# A-15430.net
KiCad netlist of a schematic drawn in EAGLE
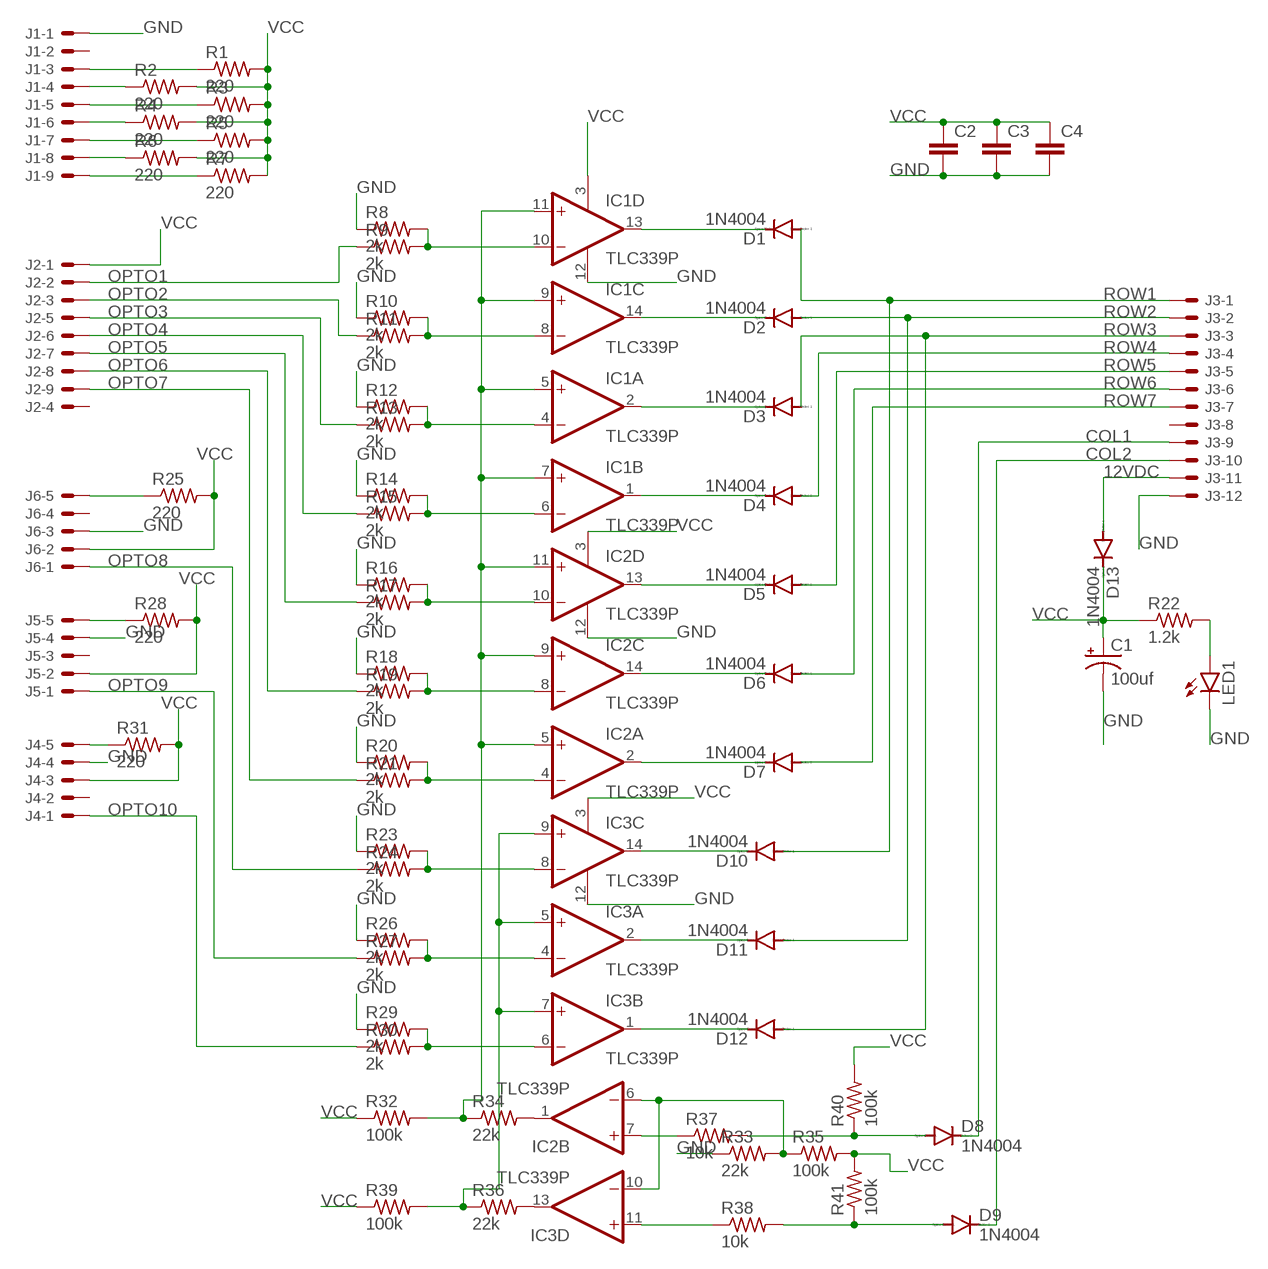
[diagram p0: schematic, sheet 1]

(export (version "E")
  (design (tool "Eeschema 10.0.6"))
  (components
    (comp (ref "C1")
      (value "100uf")
      (footprint "eagle-import:E2,5-5")
      (libsource (lib "eagle-import") (part "CPOL-USE2.5-5"))
    )
    (comp (ref "C2")
      (value "C2.5/4")
      (footprint "eagle-import:C2.5-4")
      (libsource (lib "eagle-import") (part "C2.5/4"))
    )
    (comp (ref "C3")
      (value "C2.5/4")
      (footprint "eagle-import:C2.5-4")
      (libsource (lib "eagle-import") (part "C2.5/4"))
    )
    (comp (ref "C4")
      (value "C2.5/4")
      (footprint "eagle-import:C2.5-4")
      (libsource (lib "eagle-import") (part "C2.5/4"))
    )
    (comp (ref "D1")
      (value "1N4004")
      (footprint "eagle-import:DO41-10")
      (libsource (lib "eagle-import") (part "1N4004"))
    )
    (comp (ref "D2")
      (value "1N4004")
      (footprint "eagle-import:DO41-10")
      (libsource (lib "eagle-import") (part "1N4004"))
    )
    (comp (ref "D3")
      (value "1N4004")
      (footprint "eagle-import:DO41-10")
      (libsource (lib "eagle-import") (part "1N4004"))
    )
    (comp (ref "D4")
      (value "1N4004")
      (footprint "eagle-import:DO41-10")
      (libsource (lib "eagle-import") (part "1N4004"))
    )
    (comp (ref "D5")
      (value "1N4004")
      (footprint "eagle-import:DO41-10")
      (libsource (lib "eagle-import") (part "1N4004"))
    )
    (comp (ref "D6")
      (value "1N4004")
      (footprint "eagle-import:DO41-10")
      (libsource (lib "eagle-import") (part "1N4004"))
    )
    (comp (ref "D7")
      (value "1N4004")
      (footprint "eagle-import:DO41-10")
      (libsource (lib "eagle-import") (part "1N4004"))
    )
    (comp (ref "D8")
      (value "1N4004")
      (footprint "eagle-import:DO41-10")
      (libsource (lib "eagle-import") (part "1N4004"))
    )
    (comp (ref "D9")
      (value "1N4004")
      (footprint "eagle-import:DO41-10")
      (libsource (lib "eagle-import") (part "1N4004"))
    )
    (comp (ref "D10")
      (value "1N4004")
      (footprint "eagle-import:DO41-10")
      (libsource (lib "eagle-import") (part "1N4004"))
    )
    (comp (ref "D11")
      (value "1N4004")
      (footprint "eagle-import:DO41-10")
      (libsource (lib "eagle-import") (part "1N4004"))
    )
    (comp (ref "D12")
      (value "1N4004")
      (footprint "eagle-import:DO41-10")
      (libsource (lib "eagle-import") (part "1N4004"))
    )
    (comp (ref "D13")
      (value "1N4004")
      (footprint "eagle-import:DO41-10")
      (libsource (lib "eagle-import") (part "1N4004"))
    )
    (comp (ref "IC1")
      (value "TLC339P")
      (footprint "eagle-import:DIL14")
      (libsource (lib "eagle-import") (part "TLC339P"))
    )
    (comp (ref "IC2")
      (value "TLC339P")
      (footprint "eagle-import:DIL14")
      (libsource (lib "eagle-import") (part "TLC339P"))
    )
    (comp (ref "IC3")
      (value "TLC339P")
      (footprint "eagle-import:DIL14")
      (libsource (lib "eagle-import") (part "TLC339P"))
    )
    (comp (ref "J1")
      (value "KK-156-9")
      (footprint "eagle-import:KK-156-9")
      (libsource (lib "eagle-import") (part "KK-156-9"))
    )
    (comp (ref "J2")
      (value "KK-156-9")
      (footprint "eagle-import:KK-156-9")
      (libsource (lib "eagle-import") (part "KK-156-9"))
    )
    (comp (ref "J3")
      (value "KK-156-12")
      (footprint "eagle-import:KK-156-12")
      (libsource (lib "eagle-import") (part "KK-156-12"))
    )
    (comp (ref "J4")
      (value "KK-156-5")
      (footprint "eagle-import:KK-156-5")
      (libsource (lib "eagle-import") (part "KK-156-5"))
    )
    (comp (ref "J5")
      (value "KK-156-5")
      (footprint "eagle-import:KK-156-5")
      (libsource (lib "eagle-import") (part "KK-156-5"))
    )
    (comp (ref "J6")
      (value "KK-156-5")
      (footprint "eagle-import:KK-156-5")
      (libsource (lib "eagle-import") (part "KK-156-5"))
    )
    (comp (ref "LED1")
      (value "LED5MM")
      (footprint "eagle-import:LED5MM")
      (libsource (lib "eagle-import") (part "LED5MM"))
    )
    (comp (ref "R1")
      (value "220")
      (footprint "eagle-import:0617_22")
      (libsource (lib "eagle-import") (part "R-US_0617/22"))
    )
    (comp (ref "R2")
      (value "220")
      (footprint "eagle-import:0617_22")
      (libsource (lib "eagle-import") (part "R-US_0617/22"))
    )
    (comp (ref "R3")
      (value "220")
      (footprint "eagle-import:0617_22")
      (libsource (lib "eagle-import") (part "R-US_0617/22"))
    )
    (comp (ref "R4")
      (value "220")
      (footprint "eagle-import:0617_22")
      (libsource (lib "eagle-import") (part "R-US_0617/22"))
    )
    (comp (ref "R5")
      (value "220")
      (footprint "eagle-import:0617_22")
      (libsource (lib "eagle-import") (part "R-US_0617/22"))
    )
    (comp (ref "R6")
      (value "220")
      (footprint "eagle-import:0617_22")
      (libsource (lib "eagle-import") (part "R-US_0617/22"))
    )
    (comp (ref "R7")
      (value "220")
      (footprint "eagle-import:0617_22")
      (libsource (lib "eagle-import") (part "R-US_0617/22"))
    )
    (comp (ref "R8")
      (value "2k")
      (footprint "eagle-import:0207_10")
      (libsource (lib "eagle-import") (part "R-US_0207/10"))
    )
    (comp (ref "R9")
      (value "2k")
      (footprint "eagle-import:0207_10")
      (libsource (lib "eagle-import") (part "R-US_0207/10"))
    )
    (comp (ref "R10")
      (value "2k")
      (footprint "eagle-import:0207_10")
      (libsource (lib "eagle-import") (part "R-US_0207/10"))
    )
    (comp (ref "R11")
      (value "2k")
      (footprint "eagle-import:0207_10")
      (libsource (lib "eagle-import") (part "R-US_0207/10"))
    )
    (comp (ref "R12")
      (value "2k")
      (footprint "eagle-import:0207_10")
      (libsource (lib "eagle-import") (part "R-US_0207/10"))
    )
    (comp (ref "R13")
      (value "2k")
      (footprint "eagle-import:0207_10")
      (libsource (lib "eagle-import") (part "R-US_0207/10"))
    )
    (comp (ref "R14")
      (value "2k")
      (footprint "eagle-import:0207_10")
      (libsource (lib "eagle-import") (part "R-US_0207/10"))
    )
    (comp (ref "R15")
      (value "2k")
      (footprint "eagle-import:0207_10")
      (libsource (lib "eagle-import") (part "R-US_0207/10"))
    )
    (comp (ref "R16")
      (value "2k")
      (footprint "eagle-import:0207_10")
      (libsource (lib "eagle-import") (part "R-US_0207/10"))
    )
    (comp (ref "R17")
      (value "2k")
      (footprint "eagle-import:0207_10")
      (libsource (lib "eagle-import") (part "R-US_0207/10"))
    )
    (comp (ref "R18")
      (value "2k")
      (footprint "eagle-import:0207_10")
      (libsource (lib "eagle-import") (part "R-US_0207/10"))
    )
    (comp (ref "R19")
      (value "2k")
      (footprint "eagle-import:0207_10")
      (libsource (lib "eagle-import") (part "R-US_0207/10"))
    )
    (comp (ref "R20")
      (value "2k")
      (footprint "eagle-import:0207_10")
      (libsource (lib "eagle-import") (part "R-US_0207/10"))
    )
    (comp (ref "R21")
      (value "2k")
      (footprint "eagle-import:0207_10")
      (libsource (lib "eagle-import") (part "R-US_0207/10"))
    )
    (comp (ref "R22")
      (value "1.2k")
      (footprint "eagle-import:0207_10")
      (libsource (lib "eagle-import") (part "R-US_0207/10"))
    )
    (comp (ref "R23")
      (value "2k")
      (footprint "eagle-import:0207_10")
      (libsource (lib "eagle-import") (part "R-US_0207/10"))
    )
    (comp (ref "R24")
      (value "2k")
      (footprint "eagle-import:0207_10")
      (libsource (lib "eagle-import") (part "R-US_0207/10"))
    )
    (comp (ref "R25")
      (value "220")
      (footprint "eagle-import:0617_22")
      (libsource (lib "eagle-import") (part "R-US_0617/22"))
    )
    (comp (ref "R26")
      (value "2k")
      (footprint "eagle-import:0207_10")
      (libsource (lib "eagle-import") (part "R-US_0207/10"))
    )
    (comp (ref "R27")
      (value "2k")
      (footprint "eagle-import:0207_10")
      (libsource (lib "eagle-import") (part "R-US_0207/10"))
    )
    (comp (ref "R28")
      (value "220")
      (footprint "eagle-import:0617_22")
      (libsource (lib "eagle-import") (part "R-US_0617/22"))
    )
    (comp (ref "R29")
      (value "2k")
      (footprint "eagle-import:0207_10")
      (libsource (lib "eagle-import") (part "R-US_0207/10"))
    )
    (comp (ref "R30")
      (value "2k")
      (footprint "eagle-import:0207_10")
      (libsource (lib "eagle-import") (part "R-US_0207/10"))
    )
    (comp (ref "R31")
      (value "220")
      (footprint "eagle-import:0617_22")
      (libsource (lib "eagle-import") (part "R-US_0617/22"))
    )
    (comp (ref "R32")
      (value "100k")
      (footprint "eagle-import:0207_10")
      (libsource (lib "eagle-import") (part "R-US_0207/10"))
    )
    (comp (ref "R33")
      (value "22k")
      (footprint "eagle-import:0207_10")
      (libsource (lib "eagle-import") (part "R-US_0207/10"))
    )
    (comp (ref "R34")
      (value "22k")
      (footprint "eagle-import:0207_10")
      (libsource (lib "eagle-import") (part "R-US_0207/10"))
    )
    (comp (ref "R35")
      (value "100k")
      (footprint "eagle-import:0207_10")
      (libsource (lib "eagle-import") (part "R-US_0207/10"))
    )
    (comp (ref "R36")
      (value "22k")
      (footprint "eagle-import:0207_10")
      (libsource (lib "eagle-import") (part "R-US_0207/10"))
    )
    (comp (ref "R37")
      (value "10k")
      (footprint "eagle-import:0207_10")
      (libsource (lib "eagle-import") (part "R-US_0207/10"))
    )
    (comp (ref "R38")
      (value "10k")
      (footprint "eagle-import:0207_10")
      (libsource (lib "eagle-import") (part "R-US_0207/10"))
    )
    (comp (ref "R39")
      (value "100k")
      (footprint "eagle-import:0207_10")
      (libsource (lib "eagle-import") (part "R-US_0207/10"))
    )
    (comp (ref "R40")
      (value "100k")
      (footprint "eagle-import:0207_10")
      (libsource (lib "eagle-import") (part "R-US_0207/10"))
    )
    (comp (ref "R41")
      (value "100k")
      (footprint "eagle-import:0207_10")
      (libsource (lib "eagle-import") (part "R-US_0207/10"))
    )
  )
  (nets
    (net (code "1") (name "/12VDC") (class "Default")
      (node (ref "D13") (pin "A") (pinfunction "A_A") (pintype "passive"))
      (node (ref "J3") (pin "11") (pinfunction "S_11") (pintype "passive"))
    )
    (net (code "2") (name "/COL1") (class "Default")
      (node (ref "D8") (pin "C") (pinfunction "C_C") (pintype "passive"))
      (node (ref "J3") (pin "9") (pinfunction "S_9") (pintype "passive"))
    )
    (net (code "3") (name "/COL2") (class "Default")
      (node (ref "D9") (pin "C") (pinfunction "C_C") (pintype "passive"))
      (node (ref "J3") (pin "10") (pinfunction "S_10") (pintype "passive"))
    )
    (net (code "4") (name "/GND") (class "Default")
      (node (ref "C1") (pin "-") (pinfunction "-_-") (pintype "passive"))
      (node (ref "C2") (pin "2") (pinfunction "2_2") (pintype "passive"))
      (node (ref "C3") (pin "2") (pinfunction "2_2") (pintype "passive"))
      (node (ref "C4") (pin "2") (pinfunction "2_2") (pintype "passive"))
      (node (ref "IC1") (pin "12") (pinfunction "V-_12") (pintype "power_in"))
      (node (ref "IC2") (pin "12") (pinfunction "V-_12") (pintype "power_in"))
      (node (ref "IC3") (pin "12") (pinfunction "V-_12") (pintype "power_in"))
      (node (ref "J1") (pin "1") (pinfunction "S_1") (pintype "passive"))
      (node (ref "J3") (pin "12") (pinfunction "S_12") (pintype "passive"))
      (node (ref "J4") (pin "4") (pinfunction "S_4") (pintype "passive"))
      (node (ref "J5") (pin "4") (pinfunction "S_4") (pintype "passive"))
      (node (ref "J6") (pin "3") (pinfunction "S_3") (pintype "passive"))
      (node (ref "LED1") (pin "K") (pinfunction "C_K") (pintype "passive"))
      (node (ref "R10") (pin "1") (pinfunction "1_1") (pintype "passive"))
      (node (ref "R12") (pin "1") (pinfunction "1_1") (pintype "passive"))
      (node (ref "R14") (pin "1") (pinfunction "1_1") (pintype "passive"))
      (node (ref "R16") (pin "1") (pinfunction "1_1") (pintype "passive"))
      (node (ref "R18") (pin "1") (pinfunction "1_1") (pintype "passive"))
      (node (ref "R20") (pin "1") (pinfunction "1_1") (pintype "passive"))
      (node (ref "R23") (pin "1") (pinfunction "1_1") (pintype "passive"))
      (node (ref "R26") (pin "1") (pinfunction "1_1") (pintype "passive"))
      (node (ref "R29") (pin "1") (pinfunction "1_1") (pintype "passive"))
      (node (ref "R33") (pin "1") (pinfunction "1_1") (pintype "passive"))
      (node (ref "R8") (pin "1") (pinfunction "1_1") (pintype "passive"))
    )
    (net (code "5") (name "/OPTO1") (class "Default")
      (node (ref "J2") (pin "2") (pinfunction "S_2") (pintype "passive"))
      (node (ref "R9") (pin "1") (pinfunction "1_1") (pintype "passive"))
    )
    (net (code "6") (name "/OPTO2") (class "Default")
      (node (ref "J2") (pin "3") (pinfunction "S_3") (pintype "passive"))
      (node (ref "R11") (pin "1") (pinfunction "1_1") (pintype "passive"))
    )
    (net (code "7") (name "/OPTO3") (class "Default")
      (node (ref "J2") (pin "5") (pinfunction "S_5") (pintype "passive"))
      (node (ref "R13") (pin "1") (pinfunction "1_1") (pintype "passive"))
    )
    (net (code "8") (name "/OPTO4") (class "Default")
      (node (ref "J2") (pin "6") (pinfunction "S_6") (pintype "passive"))
      (node (ref "R15") (pin "1") (pinfunction "1_1") (pintype "passive"))
    )
    (net (code "9") (name "/OPTO5") (class "Default")
      (node (ref "J2") (pin "7") (pinfunction "S_7") (pintype "passive"))
      (node (ref "R17") (pin "1") (pinfunction "1_1") (pintype "passive"))
    )
    (net (code "10") (name "/OPTO6") (class "Default")
      (node (ref "J2") (pin "8") (pinfunction "S_8") (pintype "passive"))
      (node (ref "R19") (pin "1") (pinfunction "1_1") (pintype "passive"))
    )
    (net (code "11") (name "/OPTO7") (class "Default")
      (node (ref "J2") (pin "9") (pinfunction "S_9") (pintype "passive"))
      (node (ref "R21") (pin "1") (pinfunction "1_1") (pintype "passive"))
    )
    (net (code "12") (name "/OPTO8") (class "Default")
      (node (ref "J6") (pin "1") (pinfunction "S_1") (pintype "passive"))
      (node (ref "R24") (pin "1") (pinfunction "1_1") (pintype "passive"))
    )
    (net (code "13") (name "/OPTO9") (class "Default")
      (node (ref "J5") (pin "1") (pinfunction "S_1") (pintype "passive"))
      (node (ref "R27") (pin "1") (pinfunction "1_1") (pintype "passive"))
    )
    (net (code "14") (name "/OPTO10") (class "Default")
      (node (ref "J4") (pin "1") (pinfunction "S_1") (pintype "passive"))
      (node (ref "R30") (pin "1") (pinfunction "1_1") (pintype "passive"))
    )
    (net (code "15") (name "/ROW1") (class "Default")
      (node (ref "D1") (pin "A") (pinfunction "A_A") (pintype "passive"))
      (node (ref "D10") (pin "A") (pinfunction "A_A") (pintype "passive"))
      (node (ref "J3") (pin "1") (pinfunction "S_1") (pintype "passive"))
    )
    (net (code "16") (name "/ROW2") (class "Default")
      (node (ref "D11") (pin "A") (pinfunction "A_A") (pintype "passive"))
      (node (ref "D2") (pin "A") (pinfunction "A_A") (pintype "passive"))
      (node (ref "J3") (pin "2") (pinfunction "S_2") (pintype "passive"))
    )
    (net (code "17") (name "/ROW3") (class "Default")
      (node (ref "D12") (pin "A") (pinfunction "A_A") (pintype "passive"))
      (node (ref "D3") (pin "A") (pinfunction "A_A") (pintype "passive"))
      (node (ref "J3") (pin "3") (pinfunction "S_3") (pintype "passive"))
    )
    (net (code "18") (name "/ROW4") (class "Default")
      (node (ref "D4") (pin "A") (pinfunction "A_A") (pintype "passive"))
      (node (ref "J3") (pin "4") (pinfunction "S_4") (pintype "passive"))
    )
    (net (code "19") (name "/ROW5") (class "Default")
      (node (ref "D5") (pin "A") (pinfunction "A_A") (pintype "passive"))
      (node (ref "J3") (pin "5") (pinfunction "S_5") (pintype "passive"))
    )
    (net (code "20") (name "/ROW6") (class "Default")
      (node (ref "D6") (pin "A") (pinfunction "A_A") (pintype "passive"))
      (node (ref "J3") (pin "6") (pinfunction "S_6") (pintype "passive"))
    )
    (net (code "21") (name "/ROW7") (class "Default")
      (node (ref "D7") (pin "A") (pinfunction "A_A") (pintype "passive"))
      (node (ref "J3") (pin "7") (pinfunction "S_7") (pintype "passive"))
    )
    (net (code "22") (name "/VCC") (class "Default")
      (node (ref "C1") (pin "+") (pinfunction "+_+") (pintype "passive"))
      (node (ref "C2") (pin "1") (pinfunction "1_1") (pintype "passive"))
      (node (ref "C3") (pin "1") (pinfunction "1_1") (pintype "passive"))
      (node (ref "C4") (pin "1") (pinfunction "1_1") (pintype "passive"))
      (node (ref "D13") (pin "C") (pinfunction "C_C") (pintype "passive"))
      (node (ref "IC1") (pin "3") (pinfunction "V+_3") (pintype "power_in"))
      (node (ref "IC2") (pin "3") (pinfunction "V+_3") (pintype "power_in"))
      (node (ref "IC3") (pin "3") (pinfunction "V+_3") (pintype "power_in"))
      (node (ref "J2") (pin "1") (pinfunction "S_1") (pintype "passive"))
      (node (ref "J4") (pin "3") (pinfunction "S_3") (pintype "passive"))
      (node (ref "J5") (pin "2") (pinfunction "S_2") (pintype "passive"))
      (node (ref "J6") (pin "2") (pinfunction "S_2") (pintype "passive"))
      (node (ref "R1") (pin "2") (pinfunction "2_2") (pintype "passive"))
      (node (ref "R2") (pin "2") (pinfunction "2_2") (pintype "passive"))
      (node (ref "R22") (pin "1") (pinfunction "1_1") (pintype "passive"))
      (node (ref "R25") (pin "2") (pinfunction "2_2") (pintype "passive"))
      (node (ref "R28") (pin "2") (pinfunction "2_2") (pintype "passive"))
      (node (ref "R3") (pin "2") (pinfunction "2_2") (pintype "passive"))
      (node (ref "R31") (pin "2") (pinfunction "2_2") (pintype "passive"))
      (node (ref "R32") (pin "1") (pinfunction "1_1") (pintype "passive"))
      (node (ref "R35") (pin "2") (pinfunction "2_2") (pintype "passive"))
      (node (ref "R39") (pin "1") (pinfunction "1_1") (pintype "passive"))
      (node (ref "R4") (pin "2") (pinfunction "2_2") (pintype "passive"))
      (node (ref "R40") (pin "2") (pinfunction "2_2") (pintype "passive"))
      (node (ref "R41") (pin "2") (pinfunction "2_2") (pintype "passive"))
      (node (ref "R5") (pin "2") (pinfunction "2_2") (pintype "passive"))
      (node (ref "R6") (pin "2") (pinfunction "2_2") (pintype "passive"))
      (node (ref "R7") (pin "2") (pinfunction "2_2") (pintype "passive"))
    )
    (net (code "23") (name "Net-(D8-PadA)") (class "Default")
      (node (ref "D8") (pin "A") (pinfunction "A_A") (pintype "passive"))
      (node (ref "R37") (pin "2") (pinfunction "2_2") (pintype "passive"))
      (node (ref "R40") (pin "1") (pinfunction "1_1") (pintype "passive"))
    )
    (net (code "24") (name "Net-(D9-PadA)") (class "Default")
      (node (ref "D9") (pin "A") (pinfunction "A_A") (pintype "passive"))
      (node (ref "R38") (pin "2") (pinfunction "2_2") (pintype "passive"))
      (node (ref "R41") (pin "1") (pinfunction "1_1") (pintype "passive"))
    )
    (net (code "25") (name "Net-(IC1A-+IN)") (class "Default")
      (node (ref "IC1") (pin "11") (pinfunction "+IN_11") (pintype "input"))
      (node (ref "IC1") (pin "5") (pinfunction "+IN_5") (pintype "input"))
      (node (ref "IC1") (pin "7") (pinfunction "+IN_7") (pintype "input"))
      (node (ref "IC1") (pin "9") (pinfunction "+IN_9") (pintype "input"))
      (node (ref "IC2") (pin "11") (pinfunction "+IN_11") (pintype "input"))
      (node (ref "IC2") (pin "5") (pinfunction "+IN_5") (pintype "input"))
      (node (ref "IC2") (pin "9") (pinfunction "+IN_9") (pintype "input"))
      (node (ref "R32") (pin "2") (pinfunction "2_2") (pintype "passive"))
      (node (ref "R34") (pin "1") (pinfunction "1_1") (pintype "passive"))
    )
    (net (code "26") (name "Net-(IC1A--IN)") (class "Default")
      (node (ref "IC1") (pin "4") (pinfunction "-IN_4") (pintype "input"))
      (node (ref "R12") (pin "2") (pinfunction "2_2") (pintype "passive"))
      (node (ref "R13") (pin "2") (pinfunction "2_2") (pintype "passive"))
    )
    (net (code "27") (name "Net-(IC1A-OUT)") (class "Default")
      (node (ref "D3") (pin "C") (pinfunction "C_C") (pintype "passive"))
      (node (ref "IC1") (pin "2") (pinfunction "OUT_2") (pintype "output"))
    )
    (net (code "28") (name "Net-(IC1B--IN)") (class "Default")
      (node (ref "IC1") (pin "6") (pinfunction "-IN_6") (pintype "input"))
      (node (ref "R14") (pin "2") (pinfunction "2_2") (pintype "passive"))
      (node (ref "R15") (pin "2") (pinfunction "2_2") (pintype "passive"))
    )
    (net (code "29") (name "Net-(IC1B-OUT)") (class "Default")
      (node (ref "D4") (pin "C") (pinfunction "C_C") (pintype "passive"))
      (node (ref "IC1") (pin "1") (pinfunction "OUT_1") (pintype "output"))
    )
    (net (code "30") (name "Net-(IC1C--IN)") (class "Default")
      (node (ref "IC1") (pin "8") (pinfunction "-IN_8") (pintype "input"))
      (node (ref "R10") (pin "2") (pinfunction "2_2") (pintype "passive"))
      (node (ref "R11") (pin "2") (pinfunction "2_2") (pintype "passive"))
    )
    (net (code "31") (name "Net-(IC1C-OUT)") (class "Default")
      (node (ref "D2") (pin "C") (pinfunction "C_C") (pintype "passive"))
      (node (ref "IC1") (pin "14") (pinfunction "OUT_14") (pintype "output"))
    )
    (net (code "32") (name "Net-(IC1D--IN)") (class "Default")
      (node (ref "IC1") (pin "10") (pinfunction "-IN_10") (pintype "input"))
      (node (ref "R8") (pin "2") (pinfunction "2_2") (pintype "passive"))
      (node (ref "R9") (pin "2") (pinfunction "2_2") (pintype "passive"))
    )
    (net (code "33") (name "Net-(IC1D-OUT)") (class "Default")
      (node (ref "D1") (pin "C") (pinfunction "C_C") (pintype "passive"))
      (node (ref "IC1") (pin "13") (pinfunction "OUT_13") (pintype "output"))
    )
    (net (code "34") (name "Net-(IC2A--IN)") (class "Default")
      (node (ref "IC2") (pin "4") (pinfunction "-IN_4") (pintype "input"))
      (node (ref "R20") (pin "2") (pinfunction "2_2") (pintype "passive"))
      (node (ref "R21") (pin "2") (pinfunction "2_2") (pintype "passive"))
    )
    (net (code "35") (name "Net-(IC2A-OUT)") (class "Default")
      (node (ref "D7") (pin "C") (pinfunction "C_C") (pintype "passive"))
      (node (ref "IC2") (pin "2") (pinfunction "OUT_2") (pintype "output"))
    )
    (net (code "36") (name "Net-(IC2B-+IN)") (class "Default")
      (node (ref "IC2") (pin "7") (pinfunction "+IN_7") (pintype "input"))
      (node (ref "R37") (pin "1") (pinfunction "1_1") (pintype "passive"))
    )
    (net (code "37") (name "Net-(IC2B--IN)") (class "Default")
      (node (ref "IC2") (pin "6") (pinfunction "-IN_6") (pintype "input"))
      (node (ref "IC3") (pin "10") (pinfunction "-IN_10") (pintype "input"))
      (node (ref "R33") (pin "2") (pinfunction "2_2") (pintype "passive"))
      (node (ref "R35") (pin "1") (pinfunction "1_1") (pintype "passive"))
    )
    (net (code "38") (name "Net-(IC2B-OUT)") (class "Default")
      (node (ref "IC2") (pin "1") (pinfunction "OUT_1") (pintype "output"))
      (node (ref "R34") (pin "2") (pinfunction "2_2") (pintype "passive"))
    )
    (net (code "39") (name "Net-(IC2C--IN)") (class "Default")
      (node (ref "IC2") (pin "8") (pinfunction "-IN_8") (pintype "input"))
      (node (ref "R18") (pin "2") (pinfunction "2_2") (pintype "passive"))
      (node (ref "R19") (pin "2") (pinfunction "2_2") (pintype "passive"))
    )
    (net (code "40") (name "Net-(IC2C-OUT)") (class "Default")
      (node (ref "D6") (pin "C") (pinfunction "C_C") (pintype "passive"))
      (node (ref "IC2") (pin "14") (pinfunction "OUT_14") (pintype "output"))
    )
    (net (code "41") (name "Net-(IC2D--IN)") (class "Default")
      (node (ref "IC2") (pin "10") (pinfunction "-IN_10") (pintype "input"))
      (node (ref "R16") (pin "2") (pinfunction "2_2") (pintype "passive"))
      (node (ref "R17") (pin "2") (pinfunction "2_2") (pintype "passive"))
    )
    (net (code "42") (name "Net-(IC2D-OUT)") (class "Default")
      (node (ref "D5") (pin "C") (pinfunction "C_C") (pintype "passive"))
      (node (ref "IC2") (pin "13") (pinfunction "OUT_13") (pintype "output"))
    )
    (net (code "43") (name "Net-(IC3A-+IN)") (class "Default")
      (node (ref "IC3") (pin "5") (pinfunction "+IN_5") (pintype "input"))
      (node (ref "IC3") (pin "7") (pinfunction "+IN_7") (pintype "input"))
      (node (ref "IC3") (pin "9") (pinfunction "+IN_9") (pintype "input"))
      (node (ref "R36") (pin "1") (pinfunction "1_1") (pintype "passive"))
      (node (ref "R39") (pin "2") (pinfunction "2_2") (pintype "passive"))
    )
    (net (code "44") (name "Net-(IC3A--IN)") (class "Default")
      (node (ref "IC3") (pin "4") (pinfunction "-IN_4") (pintype "input"))
      (node (ref "R26") (pin "2") (pinfunction "2_2") (pintype "passive"))
      (node (ref "R27") (pin "2") (pinfunction "2_2") (pintype "passive"))
    )
    (net (code "45") (name "Net-(IC3A-OUT)") (class "Default")
      (node (ref "D11") (pin "C") (pinfunction "C_C") (pintype "passive"))
      (node (ref "IC3") (pin "2") (pinfunction "OUT_2") (pintype "output"))
    )
    (net (code "46") (name "Net-(IC3B--IN)") (class "Default")
      (node (ref "IC3") (pin "6") (pinfunction "-IN_6") (pintype "input"))
      (node (ref "R29") (pin "2") (pinfunction "2_2") (pintype "passive"))
      (node (ref "R30") (pin "2") (pinfunction "2_2") (pintype "passive"))
    )
    (net (code "47") (name "Net-(IC3B-OUT)") (class "Default")
      (node (ref "D12") (pin "C") (pinfunction "C_C") (pintype "passive"))
      (node (ref "IC3") (pin "1") (pinfunction "OUT_1") (pintype "output"))
    )
    (net (code "48") (name "Net-(IC3C--IN)") (class "Default")
      (node (ref "IC3") (pin "8") (pinfunction "-IN_8") (pintype "input"))
      (node (ref "R23") (pin "2") (pinfunction "2_2") (pintype "passive"))
      (node (ref "R24") (pin "2") (pinfunction "2_2") (pintype "passive"))
    )
    (net (code "49") (name "Net-(IC3C-OUT)") (class "Default")
      (node (ref "D10") (pin "C") (pinfunction "C_C") (pintype "passive"))
      (node (ref "IC3") (pin "14") (pinfunction "OUT_14") (pintype "output"))
    )
    (net (code "50") (name "Net-(IC3D-+IN)") (class "Default")
      (node (ref "IC3") (pin "11") (pinfunction "+IN_11") (pintype "input"))
      (node (ref "R38") (pin "1") (pinfunction "1_1") (pintype "passive"))
    )
    (net (code "51") (name "Net-(IC3D-OUT)") (class "Default")
      (node (ref "IC3") (pin "13") (pinfunction "OUT_13") (pintype "output"))
      (node (ref "R36") (pin "2") (pinfunction "2_2") (pintype "passive"))
    )
    (net (code "52") (name "Net-(J1C-S)") (class "Default")
      (node (ref "J1") (pin "3") (pinfunction "S_3") (pintype "passive"))
      (node (ref "R1") (pin "1") (pinfunction "1_1") (pintype "passive"))
    )
    (net (code "53") (name "Net-(J1D-S)") (class "Default")
      (node (ref "J1") (pin "4") (pinfunction "S_4") (pintype "passive"))
      (node (ref "R2") (pin "1") (pinfunction "1_1") (pintype "passive"))
    )
    (net (code "54") (name "Net-(J1E-S)") (class "Default")
      (node (ref "J1") (pin "5") (pinfunction "S_5") (pintype "passive"))
      (node (ref "R3") (pin "1") (pinfunction "1_1") (pintype "passive"))
    )
    (net (code "55") (name "Net-(J1F-S)") (class "Default")
      (node (ref "J1") (pin "6") (pinfunction "S_6") (pintype "passive"))
      (node (ref "R4") (pin "1") (pinfunction "1_1") (pintype "passive"))
    )
    (net (code "56") (name "Net-(J1G-S)") (class "Default")
      (node (ref "J1") (pin "7") (pinfunction "S_7") (pintype "passive"))
      (node (ref "R5") (pin "1") (pinfunction "1_1") (pintype "passive"))
    )
    (net (code "57") (name "Net-(J1H-S)") (class "Default")
      (node (ref "J1") (pin "8") (pinfunction "S_8") (pintype "passive"))
      (node (ref "R6") (pin "1") (pinfunction "1_1") (pintype "passive"))
    )
    (net (code "58") (name "Net-(J1I-S)") (class "Default")
      (node (ref "J1") (pin "9") (pinfunction "S_9") (pintype "passive"))
      (node (ref "R7") (pin "1") (pinfunction "1_1") (pintype "passive"))
    )
    (net (code "59") (name "Net-(J4E-S)") (class "Default")
      (node (ref "J4") (pin "5") (pinfunction "S_5") (pintype "passive"))
      (node (ref "R31") (pin "1") (pinfunction "1_1") (pintype "passive"))
    )
    (net (code "60") (name "Net-(J5E-S)") (class "Default")
      (node (ref "J5") (pin "5") (pinfunction "S_5") (pintype "passive"))
      (node (ref "R28") (pin "1") (pinfunction "1_1") (pintype "passive"))
    )
    (net (code "61") (name "Net-(J6E-S)") (class "Default")
      (node (ref "J6") (pin "5") (pinfunction "S_5") (pintype "passive"))
      (node (ref "R25") (pin "1") (pinfunction "1_1") (pintype "passive"))
    )
    (net (code "62") (name "Net-(LED1-PadA)") (class "Default")
      (node (ref "LED1") (pin "A") (pinfunction "A_A") (pintype "passive"))
      (node (ref "R22") (pin "2") (pinfunction "2_2") (pintype "passive"))
    )
    (net (code "63") (name "unconnected-(J1B-S-Pad2)") (class "Default")
      (node (ref "J1") (pin "2") (pinfunction "S_2") (pintype "passive"))
    )
    (net (code "64") (name "unconnected-(J2D-S-Pad4)") (class "Default")
      (node (ref "J2") (pin "4") (pinfunction "S_4") (pintype "passive"))
    )
    (net (code "65") (name "unconnected-(J3K-S-Pad8)") (class "Default")
      (node (ref "J3") (pin "8") (pinfunction "S_8") (pintype "passive"))
    )
    (net (code "66") (name "unconnected-(J4B-S-Pad2)") (class "Default")
      (node (ref "J4") (pin "2") (pinfunction "S_2") (pintype "passive"))
    )
    (net (code "67") (name "unconnected-(J5C-S-Pad3)") (class "Default")
      (node (ref "J5") (pin "3") (pinfunction "S_3") (pintype "passive"))
    )
    (net (code "68") (name "unconnected-(J6D-S-Pad4)") (class "Default")
      (node (ref "J6") (pin "4") (pinfunction "S_4") (pintype "passive"))
    )
  )
)
